# main.net
KiCad netlist of a schematic drawn in EAGLE
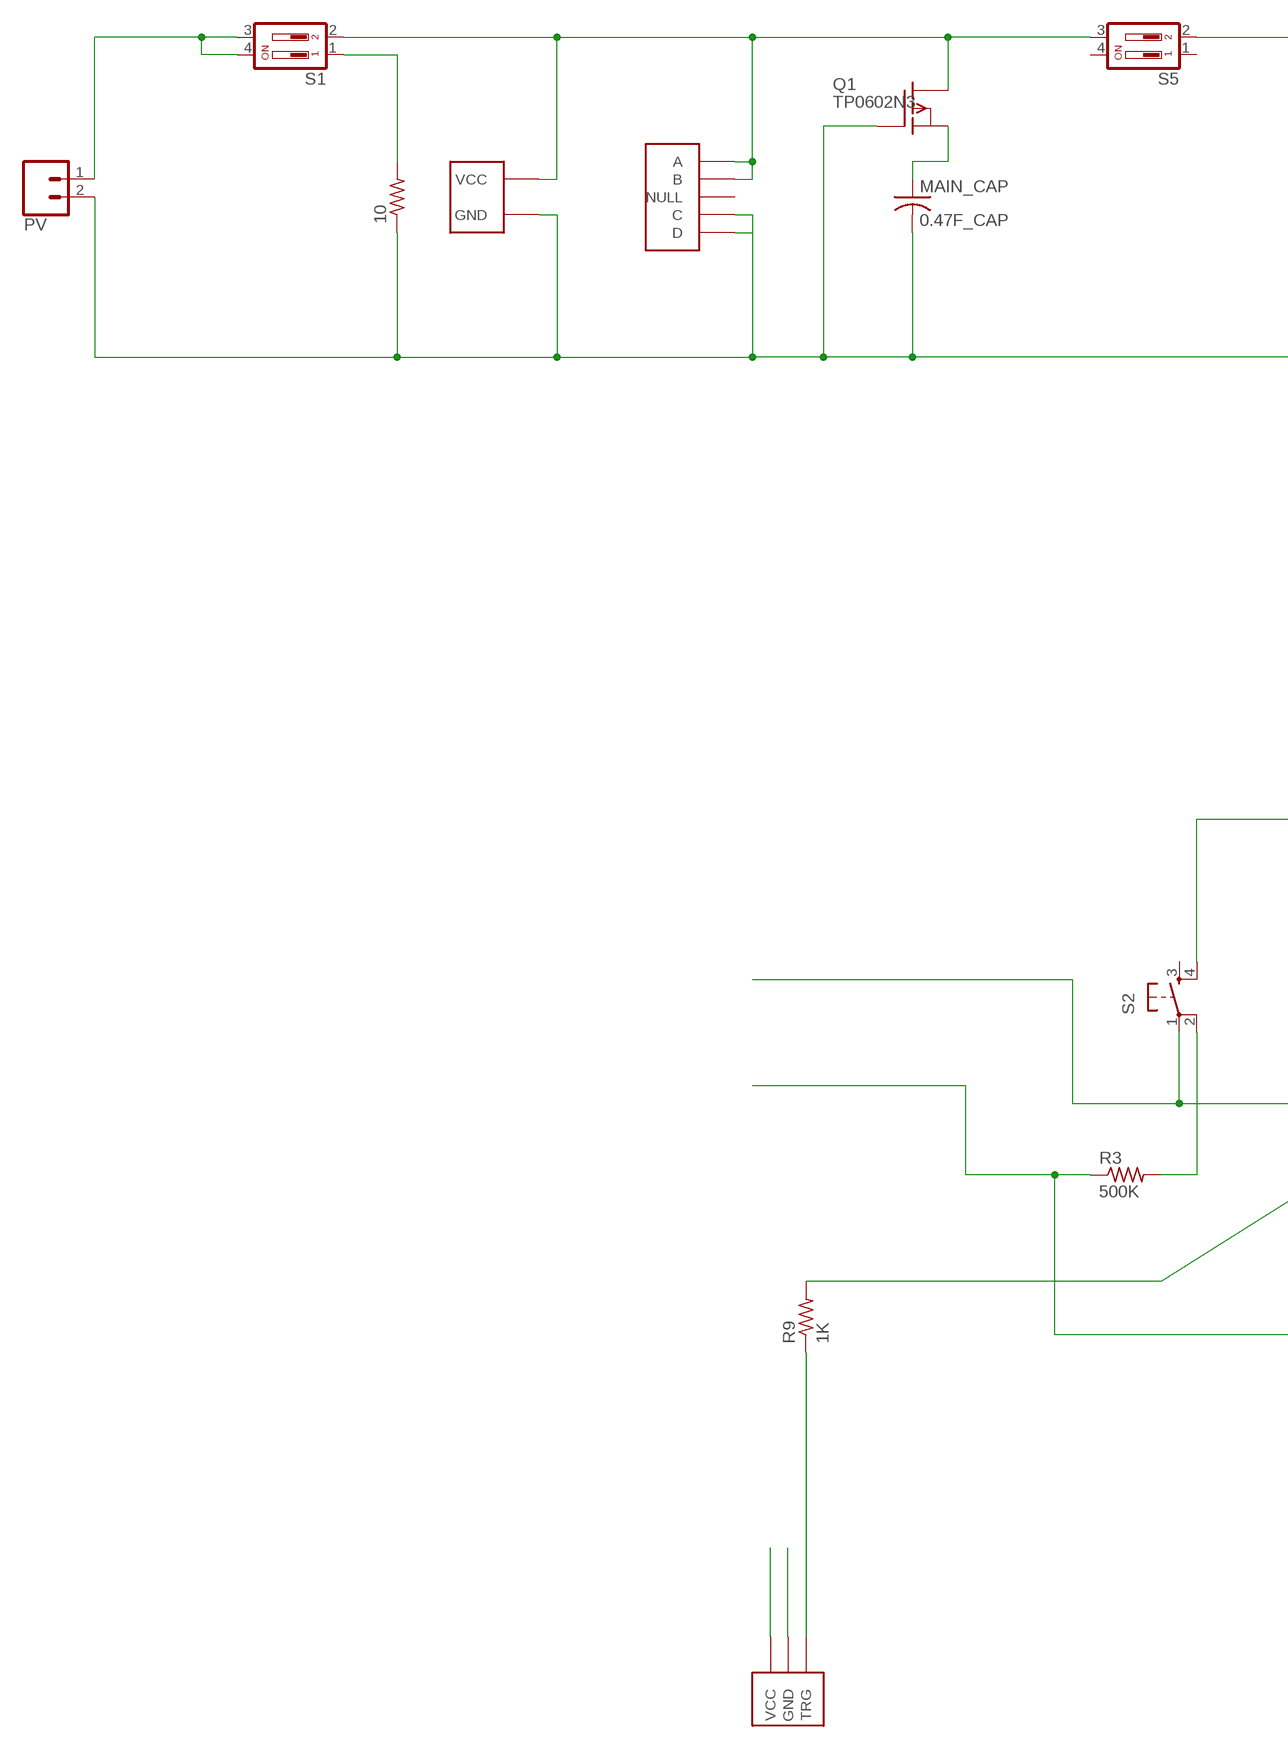
[diagram p0: schematic, sheet 1, part 1 of 2]
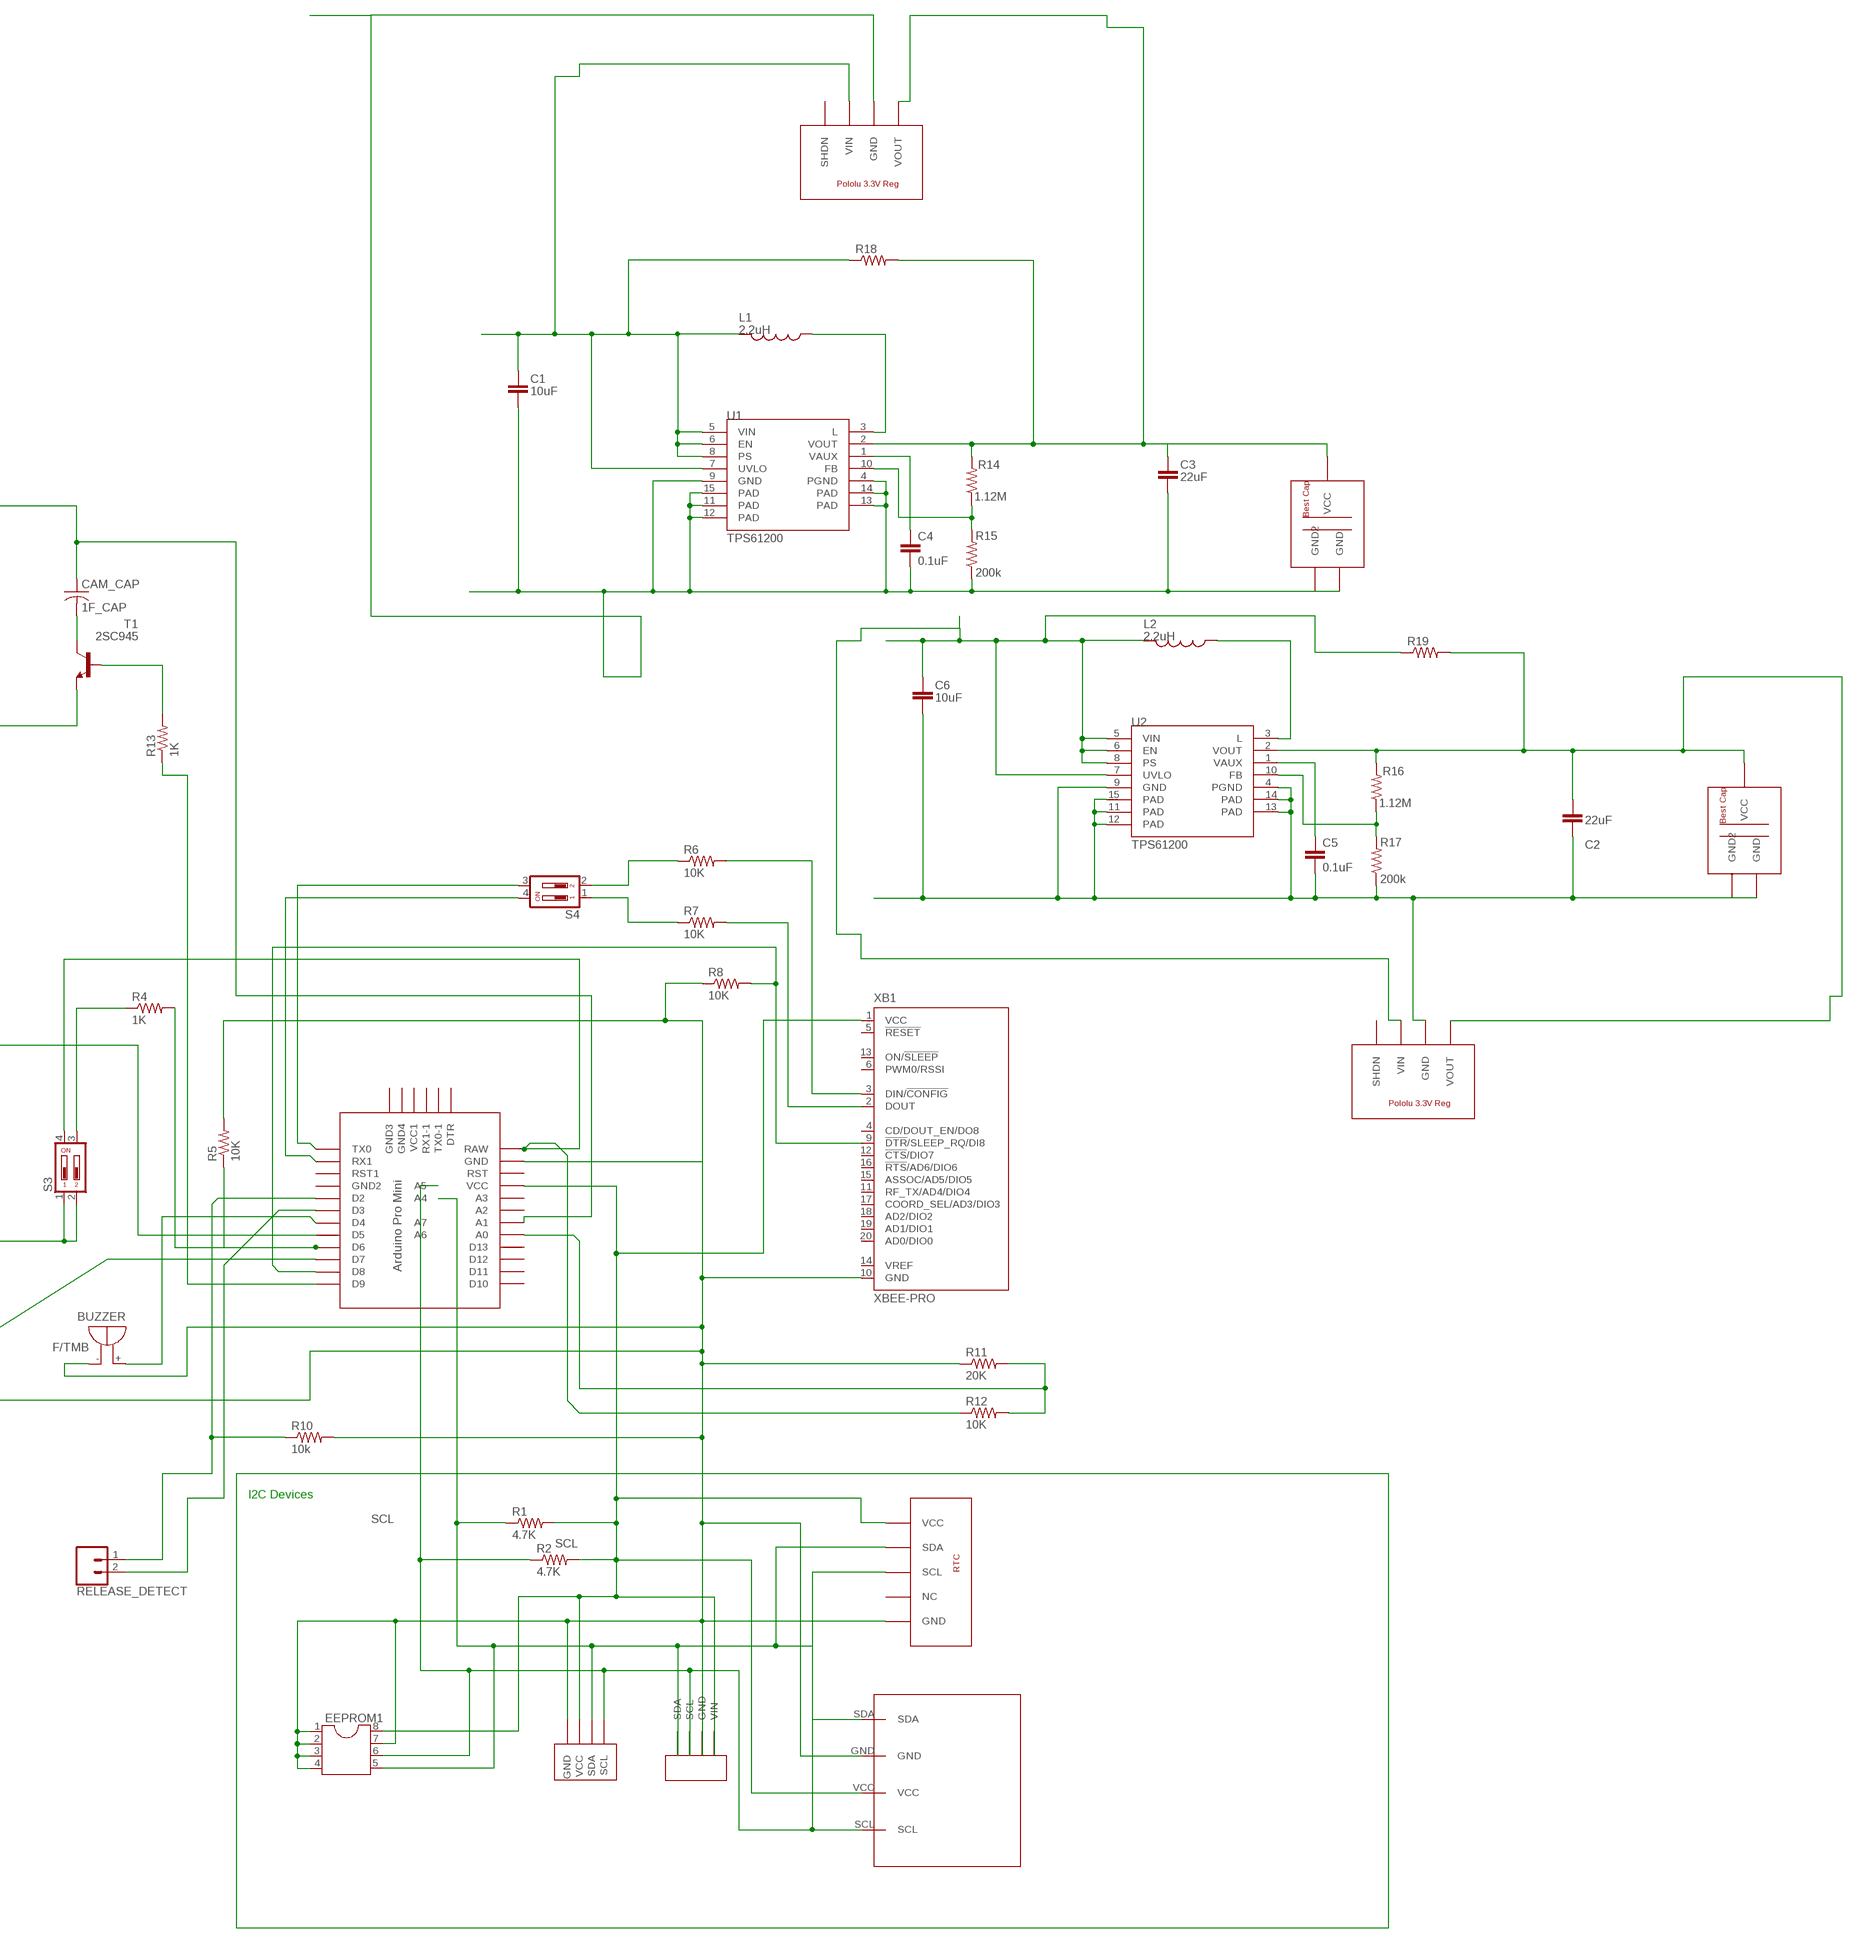
[diagram p1: schematic, sheet 1, part 2 of 2]

(export (version "E")
  (design (tool "Eeschema 10.0.6"))
  (components
    (comp (ref "10")
      (value "R-US_M1206")
      (footprint "eagle-import:M1206")
      (libsource (lib "eagle-import") (part "R-US_M1206"))
    )
    (comp (ref "BUZZER")
      (value "F/TMB")
      (footprint "eagle-import:F_TMB")
      (libsource (lib "eagle-import") (part "F/TMB"))
    )
    (comp (ref "C1")
      (value "10uF")
      (footprint "eagle-import:0805")
      (libsource (lib "eagle-import") (part "CAP0805"))
    )
    (comp (ref "C2")
      (value "22uF")
      (footprint "eagle-import:0805")
      (libsource (lib "eagle-import") (part "CAP0805"))
    )
    (comp (ref "C3")
      (value "22uF")
      (footprint "eagle-import:0805")
      (libsource (lib "eagle-import") (part "CAP0805"))
    )
    (comp (ref "C4")
      (value "0.1uF")
      (footprint "eagle-import:0805")
      (libsource (lib "eagle-import") (part "SparkFun_CAP0805"))
    )
    (comp (ref "C5")
      (value "0.1uF")
      (footprint "eagle-import:0805")
      (libsource (lib "eagle-import") (part "SparkFun_CAP0805"))
    )
    (comp (ref "C6")
      (value "10uF")
      (footprint "eagle-import:0805")
      (libsource (lib "eagle-import") (part "CAP0805"))
    )
    (comp (ref "CAM_CAP")
      (value "1F_CAP")
      (footprint "eagle-import:1F_CAP")
      (libsource (lib "eagle-import") (part "1F_CAP"))
    )
    (comp (ref "EEPROM1")
      (value "DIL8S")
      (footprint "eagle-import:SOCKET-08")
      (libsource (lib "eagle-import") (part "DIL8S"))
    )
    (comp (ref "L1")
      (value "2.2uH")
      (footprint "eagle-import:1212")
      (libsource (lib "eagle-import") (part "INDUCTOR_LIP"))
    )
    (comp (ref "L2")
      (value "2.2uH")
      (footprint "eagle-import:1212")
      (libsource (lib "eagle-import") (part "INDUCTOR_LIP"))
    )
    (comp (ref "MAIN_CAP")
      (value "0.47F_CAP")
      (footprint "eagle-import:0.47F_CAP")
      (libsource (lib "eagle-import") (part "0.47F_CAP"))
    )
    (comp (ref "PITOTTUBE")
      (value "SENSIRION")
      (footprint "eagle-import:SENSIRIONSDP810")
      (libsource (lib "eagle-import") (part "SENSIRION"))
    )
    (comp (ref "PV")
      (value "CONN_02")
      (footprint "eagle-import:1X02")
      (libsource (lib "eagle-import") (part "CONN_02"))
    )
    (comp (ref "Q1")
      (value "TP0602N3")
      (footprint "eagle-import:TO-92")
      (libsource (lib "eagle-import") (part "TP0602N3"))
    )
    (comp (ref "R1")
      (value "4.7K")
      (footprint "eagle-import:M0805")
      (libsource (lib "eagle-import") (part "R-US_M0805"))
    )
    (comp (ref "R2")
      (value "4.7K")
      (footprint "eagle-import:M0805")
      (libsource (lib "eagle-import") (part "R-US_M0805"))
    )
    (comp (ref "R3")
      (value "500K")
      (footprint "eagle-import:M0805")
      (libsource (lib "eagle-import") (part "R-US_M0805"))
    )
    (comp (ref "R4")
      (value "1K")
      (footprint "eagle-import:M0805")
      (libsource (lib "eagle-import") (part "R-US_M0805"))
    )
    (comp (ref "R5")
      (value "10K")
      (footprint "eagle-import:M0805")
      (libsource (lib "eagle-import") (part "R-US_M0805"))
    )
    (comp (ref "R6")
      (value "10K")
      (footprint "eagle-import:R0805")
      (libsource (lib "eagle-import") (part "R-US_R0805"))
    )
    (comp (ref "R7")
      (value "10K")
      (footprint "eagle-import:R0805")
      (libsource (lib "eagle-import") (part "R-US_R0805"))
    )
    (comp (ref "R8")
      (value "10K")
      (footprint "eagle-import:R0805")
      (libsource (lib "eagle-import") (part "R-US_R0805"))
    )
    (comp (ref "R9")
      (value "1K")
      (footprint "eagle-import:R0805")
      (libsource (lib "eagle-import") (part "R-US_R0805"))
    )
    (comp (ref "R10")
      (value "10k")
      (footprint "eagle-import:R0805")
      (libsource (lib "eagle-import") (part "R-US_R0805"))
    )
    (comp (ref "R11")
      (value "20K")
      (footprint "eagle-import:R0805")
      (libsource (lib "eagle-import") (part "R-US_R0805"))
    )
    (comp (ref "R12")
      (value "10K")
      (footprint "eagle-import:R0805")
      (libsource (lib "eagle-import") (part "R-US_R0805"))
    )
    (comp (ref "R13")
      (value "1K")
      (footprint "eagle-import:M0805")
      (libsource (lib "eagle-import") (part "resistor_348_R-US_M0805"))
    )
    (comp (ref "R14")
      (value "1.12M")
      (footprint "eagle-import:0805")
      (libsource (lib "eagle-import") (part "RESISTOR0805-RES"))
    )
    (comp (ref "R15")
      (value "200k")
      (footprint "eagle-import:0805")
      (libsource (lib "eagle-import") (part "RESISTOR0805-RES"))
    )
    (comp (ref "R16")
      (value "1.12M")
      (footprint "eagle-import:0805")
      (libsource (lib "eagle-import") (part "RESISTOR0805-RES"))
    )
    (comp (ref "R17")
      (value "200k")
      (footprint "eagle-import:0805")
      (libsource (lib "eagle-import") (part "RESISTOR0805-RES"))
    )
    (comp (ref "R18")
      (value "R-US_M0805")
      (footprint "eagle-import:M0805")
      (libsource (lib "eagle-import") (part "resistor_348_R-US_M0805"))
    )
    (comp (ref "R19")
      (value "R-US_R0805")
      (footprint "eagle-import:R0805")
      (libsource (lib "eagle-import") (part "resistor_348_R-US_R0805"))
    )
    (comp (ref "RELEASE_DETECT")
      (value "CONN_02")
      (footprint "eagle-import:1X02")
      (libsource (lib "eagle-import") (part "CONN_02"))
    )
    (comp (ref "S1")
      (value "DP02")
      (footprint "eagle-import:DP-02")
      (fields (field (name "MPN") "MCDP02"))
      (libsource (lib "eagle-import") (part "DP02"))
    )
    (comp (ref "S2")
      (value "TAC_SWITCHPTH")
      (footprint "eagle-import:TACTILE-PTH")
      (libsource (lib "eagle-import") (part "TAC_SWITCHPTH"))
    )
    (comp (ref "S3")
      (value "DP02")
      (footprint "eagle-import:DP-02")
      (fields (field (name "MPN") "MCDP02"))
      (libsource (lib "eagle-import") (part "DP02"))
    )
    (comp (ref "S4")
      (value "DP02")
      (footprint "eagle-import:DP-02")
      (fields (field (name "MPN") "MCDP02"))
      (libsource (lib "eagle-import") (part "DP02"))
    )
    (comp (ref "S5")
      (value "DP02")
      (footprint "eagle-import:DP-02")
      (fields (field (name "MPN") "MCDP02"))
      (libsource (lib "eagle-import") (part "DP02"))
    )
    (comp (ref "T1")
      (value "2SC945")
      (footprint "eagle-import:TO92-ECB")
      (libsource (lib "eagle-import") (part "2SC945"))
    )
    (comp (ref "U$1")
      (value "PRO-MINI-2")
      (footprint "eagle-import:PRO-MINI-2")
      (libsource (lib "eagle-import") (part "PRO-MINI-2"))
    )
    (comp (ref "U$2")
      (value "HMC883L_BREAKOUT")
      (footprint "eagle-import:HMC5833L_BREAKOUT")
      (libsource (lib "eagle-import") (part "HMC883L_BREAKOUT"))
    )
    (comp (ref "U$3")
      (value "BMP180_BREAKOUT")
      (footprint "eagle-import:BMP180_BREAKOUT")
      (libsource (lib "eagle-import") (part "BMP180_BREAKOUT"))
    )
    (comp (ref "U$4")
      (value "CAMERA_BREAKOUT")
      (footprint "eagle-import:CAMERA")
      (libsource (lib "eagle-import") (part "CAMERA_BREAKOUT"))
    )
    (comp (ref "U$5")
      (value "EXT_PWR")
      (footprint "eagle-import:EXTERNALPOWER")
      (libsource (lib "eagle-import") (part "EXT_PWR"))
    )
    (comp (ref "U$6")
      (value "VOLTMETER")
      (footprint "eagle-import:VOLTMETER")
      (libsource (lib "eagle-import") (part "VOLTMETER"))
    )
    (comp (ref "U$7")
      (value "RTC")
      (footprint "eagle-import:RTC")
      (libsource (lib "eagle-import") (part "RTC"))
    )
    (comp (ref "U$8")
      (value "BESTCAP")
      (footprint "eagle-import:BESTCAP")
      (libsource (lib "eagle-import") (part "BESTCAP"))
    )
    (comp (ref "U$9")
      (value "BESTCAP")
      (footprint "eagle-import:BESTCAP")
      (libsource (lib "eagle-import") (part "BESTCAP"))
    )
    (comp (ref "U$10")
      (value "POLOLU3VREG")
      (footprint "eagle-import:POLOLU3VREG")
      (libsource (lib "eagle-import") (part "POLOLU3VREG"))
    )
    (comp (ref "U$11")
      (value "POLOLU3VREG")
      (footprint "eagle-import:POLOLU3VREG")
      (libsource (lib "eagle-import") (part "POLOLU3VREG"))
    )
    (comp (ref "U1")
      (value "TPS61200")
      (footprint "eagle-import:QFN-10_PAD")
      (libsource (lib "eagle-import") (part "TPS61200"))
    )
    (comp (ref "U2")
      (value "TPS61200")
      (footprint "eagle-import:QFN-10_PAD")
      (libsource (lib "eagle-import") (part "TPS61200"))
    )
    (comp (ref "XB1")
      (value "XBEE-PRO")
      (footprint "eagle-import:XBEE-PRO")
      (fields (field (name "MPN") "XBP24-AWI-001"))
      (libsource (lib "eagle-import") (part "XBEE-PRO"))
    )
  )
  (nets
    (net (code "1") (name "/CAM_VIN") (class "Default")
      (node (ref "C2") (pin "1") (pinfunction "1_1") (pintype "passive"))
      (node (ref "R16") (pin "2") (pinfunction "2_2") (pintype "passive"))
      (node (ref "R19") (pin "2") (pinfunction "2_2") (pintype "passive"))
      (node (ref "U$11") (pin "VOUT") (pinfunction "VOUT_VOUT") (pintype "bidirectional"))
      (node (ref "U$4") (pin "VCC") (pinfunction "VCC_VCC") (pintype "bidirectional"))
      (node (ref "U$9") (pin "VCC") (pinfunction "VCC_VCC") (pintype "bidirectional"))
      (node (ref "U2") (pin "2") (pinfunction "VOUT_2") (pintype "passive"))
    )
    (net (code "2") (name "/CAP_VIN") (class "Default")
      (node (ref "C6") (pin "1") (pinfunction "1_1") (pintype "passive"))
      (node (ref "CAM_CAP") (pin "+") (pinfunction "+_+") (pintype "passive"))
      (node (ref "L2") (pin "P$2") (pinfunction "2_P$2") (pintype "passive"))
      (node (ref "R19") (pin "1") (pinfunction "1_1") (pintype "passive"))
      (node (ref "S5") (pin "2") (pinfunction "2_2") (pintype "passive"))
      (node (ref "U$1") (pin "A1") (pinfunction "A1_A1") (pintype "bidirectional"))
      (node (ref "U$11") (pin "VIN") (pinfunction "VIN_VIN") (pintype "bidirectional"))
      (node (ref "U2") (pin "5") (pinfunction "VIN_5") (pintype "power_in"))
      (node (ref "U2") (pin "6") (pinfunction "EN_6") (pintype "input"))
      (node (ref "U2") (pin "7") (pinfunction "UVLO_7") (pintype "passive"))
      (node (ref "U2") (pin "8") (pinfunction "PS_8") (pintype "input"))
    )
    (net (code "3") (name "/GND") (class "Default")
      (node (ref "10") (pin "1") (pinfunction "1_1") (pintype "passive"))
      (node (ref "BUZZER") (pin "-") (pinfunction "-_-") (pintype "passive"))
      (node (ref "C1") (pin "2") (pinfunction "2_2") (pintype "passive"))
      (node (ref "C2") (pin "2") (pinfunction "2_2") (pintype "passive"))
      (node (ref "C3") (pin "2") (pinfunction "2_2") (pintype "passive"))
      (node (ref "C4") (pin "2") (pinfunction "2_2") (pintype "passive"))
      (node (ref "C5") (pin "2") (pinfunction "2_2") (pintype "passive"))
      (node (ref "C6") (pin "2") (pinfunction "2_2") (pintype "passive"))
      (node (ref "EEPROM1") (pin "1") (pinfunction "1_1") (pintype "passive"))
      (node (ref "EEPROM1") (pin "2") (pinfunction "2_2") (pintype "passive"))
      (node (ref "EEPROM1") (pin "3") (pinfunction "3_3") (pintype "passive"))
      (node (ref "EEPROM1") (pin "4") (pinfunction "4_4") (pintype "passive"))
      (node (ref "EEPROM1") (pin "7") (pinfunction "7_7") (pintype "passive"))
      (node (ref "MAIN_CAP") (pin "-") (pinfunction "-_-") (pintype "passive"))
      (node (ref "PITOTTUBE") (pin "GND") (pinfunction "GND_GND") (pintype "bidirectional"))
      (node (ref "PV") (pin "2") (pinfunction "2_2") (pintype "passive"))
      (node (ref "Q1") (pin "2") (pinfunction "G_2") (pintype "passive"))
      (node (ref "R10") (pin "2") (pinfunction "2_2") (pintype "passive"))
      (node (ref "R11") (pin "1") (pinfunction "1_1") (pintype "passive"))
      (node (ref "R15") (pin "1") (pinfunction "1_1") (pintype "passive"))
      (node (ref "R17") (pin "1") (pinfunction "1_1") (pintype "passive"))
      (node (ref "R3") (pin "1") (pinfunction "1_1") (pintype "passive"))
      (node (ref "R5") (pin "2") (pinfunction "2_2") (pintype "passive"))
      (node (ref "R8") (pin "1") (pinfunction "1_1") (pintype "passive"))
      (node (ref "T1") (pin "E") (pinfunction "E_E") (pintype "passive"))
      (node (ref "U$1") (pin "GND") (pinfunction "GND_GND") (pintype "bidirectional"))
      (node (ref "U$10") (pin "GND") (pinfunction "GND_GND") (pintype "bidirectional"))
      (node (ref "U$11") (pin "GND") (pinfunction "GND_GND") (pintype "bidirectional"))
      (node (ref "U$2") (pin "GND") (pinfunction "GND_GND") (pintype "bidirectional"))
      (node (ref "U$3") (pin "GND") (pinfunction "GND_GND") (pintype "bidirectional"))
      (node (ref "U$4") (pin "GND") (pinfunction "GND_GND") (pintype "bidirectional"))
      (node (ref "U$5") (pin "GND") (pinfunction "GND_GND") (pintype "bidirectional"))
      (node (ref "U$6") (pin "C") (pinfunction "C_C") (pintype "bidirectional"))
      (node (ref "U$6") (pin "D") (pinfunction "D_D") (pintype "bidirectional"))
      (node (ref "U$7") (pin "GND") (pinfunction "GND_GND") (pintype "bidirectional"))
      (node (ref "U$8") (pin "GND") (pinfunction "GND_GND") (pintype "bidirectional"))
      (node (ref "U$8") (pin "GND2") (pinfunction "GND2_GND2") (pintype "bidirectional"))
      (node (ref "U$9") (pin "GND") (pinfunction "GND_GND") (pintype "bidirectional"))
      (node (ref "U$9") (pin "GND2") (pinfunction "GND2_GND2") (pintype "bidirectional"))
      (node (ref "U1") (pin "11") (pinfunction "PAD_11") (pintype "power_in"))
      (node (ref "U1") (pin "12") (pinfunction "PAD_12") (pintype "power_in"))
      (node (ref "U1") (pin "13") (pinfunction "PAD_13") (pintype "power_in"))
      (node (ref "U1") (pin "14") (pinfunction "PAD_14") (pintype "power_in"))
      (node (ref "U1") (pin "15") (pinfunction "PAD_15") (pintype "power_in"))
      (node (ref "U1") (pin "4") (pinfunction "PGND_4") (pintype "power_in"))
      (node (ref "U1") (pin "9") (pinfunction "GND_9") (pintype "power_in"))
      (node (ref "U2") (pin "11") (pinfunction "PAD_11") (pintype "power_in"))
      (node (ref "U2") (pin "12") (pinfunction "PAD_12") (pintype "power_in"))
      (node (ref "U2") (pin "13") (pinfunction "PAD_13") (pintype "power_in"))
      (node (ref "U2") (pin "14") (pinfunction "PAD_14") (pintype "power_in"))
      (node (ref "U2") (pin "15") (pinfunction "PAD_15") (pintype "power_in"))
      (node (ref "U2") (pin "4") (pinfunction "PGND_4") (pintype "power_in"))
      (node (ref "U2") (pin "9") (pinfunction "GND_9") (pintype "power_in"))
      (node (ref "XB1") (pin "10") (pinfunction "GND_10") (pintype "power_in"))
    )
    (net (code "4") (name "/MAIN_VIN") (class "Default")
      (node (ref "C3") (pin "1") (pinfunction "1_1") (pintype "passive"))
      (node (ref "R14") (pin "2") (pinfunction "2_2") (pintype "passive"))
      (node (ref "R18") (pin "2") (pinfunction "2_2") (pintype "passive"))
      (node (ref "S2") (pin "1") (pinfunction "1_1") (pintype "passive"))
      (node (ref "S3") (pin "1") (pinfunction "1_1") (pintype "passive"))
      (node (ref "S3") (pin "2") (pinfunction "2_2") (pintype "passive"))
      (node (ref "U$10") (pin "VOUT") (pinfunction "VOUT_VOUT") (pintype "bidirectional"))
      (node (ref "U$8") (pin "VCC") (pinfunction "VCC_VCC") (pintype "bidirectional"))
      (node (ref "U1") (pin "2") (pinfunction "VOUT_2") (pintype "passive"))
    )
    (net (code "5") (name "/SCL") (class "Default")
      (node (ref "EEPROM1") (pin "6") (pinfunction "6_6") (pintype "passive"))
      (node (ref "PITOTTUBE") (pin "SCL") (pinfunction "SCL_SCL") (pintype "bidirectional"))
      (node (ref "R2") (pin "1") (pinfunction "1_1") (pintype "passive"))
      (node (ref "U$1") (pin "A5") (pinfunction "A5_A5") (pintype "bidirectional"))
      (node (ref "U$2") (pin "SCL") (pinfunction "SCL_SCL") (pintype "bidirectional"))
      (node (ref "U$3") (pin "SCL") (pinfunction "SCL_SCL") (pintype "bidirectional"))
      (node (ref "U$7") (pin "SCL") (pinfunction "SCL_SCL") (pintype "bidirectional"))
    )
    (net (code "6") (name "/VIN") (class "Default")
      (node (ref "C1") (pin "1") (pinfunction "1_1") (pintype "passive"))
      (node (ref "L1") (pin "P$2") (pinfunction "2_P$2") (pintype "passive"))
      (node (ref "MAIN_CAP") (pin "+") (pinfunction "+_+") (pintype "passive"))
      (node (ref "Q1") (pin "1") (pinfunction "S_1") (pintype "passive"))
      (node (ref "R18") (pin "1") (pinfunction "1_1") (pintype "passive"))
      (node (ref "U$10") (pin "VIN") (pinfunction "VIN_VIN") (pintype "bidirectional"))
      (node (ref "U1") (pin "5") (pinfunction "VIN_5") (pintype "power_in"))
      (node (ref "U1") (pin "6") (pinfunction "EN_6") (pintype "input"))
      (node (ref "U1") (pin "7") (pinfunction "UVLO_7") (pintype "passive"))
      (node (ref "U1") (pin "8") (pinfunction "PS_8") (pintype "input"))
    )
    (net (code "7") (name "Net-(10-Pad2)") (class "Default")
      (node (ref "10") (pin "2") (pinfunction "2_2") (pintype "passive"))
      (node (ref "S1") (pin "1") (pinfunction "1_1") (pintype "passive"))
    )
    (net (code "8") (name "Net-(BUZZER-Pad+)") (class "Default")
      (node (ref "BUZZER") (pin "+") (pinfunction "+_+") (pintype "passive"))
      (node (ref "U$1") (pin "D4") (pinfunction "D4_D4") (pintype "bidirectional"))
    )
    (net (code "9") (name "Net-(CAM_CAP-Pad-)") (class "Default")
      (node (ref "CAM_CAP") (pin "-") (pinfunction "-_-") (pintype "passive"))
      (node (ref "T1") (pin "C") (pinfunction "C_C") (pintype "passive"))
    )
    (net (code "10") (name "Net-(EEPROM1-Pad5)") (class "Default")
      (node (ref "EEPROM1") (pin "5") (pinfunction "5_5") (pintype "passive"))
      (node (ref "PITOTTUBE") (pin "SDA") (pinfunction "SDA_SDA") (pintype "bidirectional"))
      (node (ref "R1") (pin "1") (pinfunction "1_1") (pintype "passive"))
      (node (ref "U$1") (pin "A4") (pinfunction "A4_A4") (pintype "bidirectional"))
      (node (ref "U$2") (pin "SDA") (pinfunction "SDA_SDA") (pintype "bidirectional"))
      (node (ref "U$3") (pin "SDA") (pinfunction "SDA_SDA") (pintype "bidirectional"))
      (node (ref "U$7") (pin "SDA") (pinfunction "SDA_SDA") (pintype "bidirectional"))
    )
    (net (code "11") (name "Net-(L1-1)") (class "Default")
      (node (ref "L1") (pin "P$1") (pinfunction "1_P$1") (pintype "passive"))
      (node (ref "U1") (pin "3") (pinfunction "L_3") (pintype "passive"))
    )
    (net (code "12") (name "Net-(L2-1)") (class "Default")
      (node (ref "L2") (pin "P$1") (pinfunction "1_P$1") (pintype "passive"))
      (node (ref "U2") (pin "3") (pinfunction "L_3") (pintype "passive"))
    )
    (net (code "13") (name "Net-(PV-Pad1)") (class "Default")
      (node (ref "PV") (pin "1") (pinfunction "1_1") (pintype "passive"))
      (node (ref "S1") (pin "3") (pinfunction "3_3") (pintype "passive"))
      (node (ref "S1") (pin "4") (pinfunction "4_4") (pintype "passive"))
    )
    (net (code "14") (name "Net-(Q1-D)") (class "Default")
      (node (ref "Q1") (pin "3") (pinfunction "D_3") (pintype "passive"))
      (node (ref "S1") (pin "2") (pinfunction "2_2") (pintype "passive"))
      (node (ref "S5") (pin "3") (pinfunction "3_3") (pintype "passive"))
      (node (ref "U$5") (pin "VCC") (pinfunction "VCC_VCC") (pintype "bidirectional"))
      (node (ref "U$6") (pin "A") (pinfunction "A_A") (pintype "bidirectional"))
      (node (ref "U$6") (pin "B") (pinfunction "B_B") (pintype "bidirectional"))
    )
    (net (code "15") (name "Net-(R3-Pad2)") (class "Default")
      (node (ref "R3") (pin "2") (pinfunction "2_2") (pintype "passive"))
      (node (ref "S2") (pin "2") (pinfunction "2_2") (pintype "passive"))
    )
    (net (code "16") (name "Net-(R4-Pad1)") (class "Default")
      (node (ref "R4") (pin "1") (pinfunction "1_1") (pintype "passive"))
      (node (ref "S3") (pin "3") (pinfunction "3_3") (pintype "passive"))
    )
    (net (code "17") (name "Net-(R4-Pad2)") (class "Default")
      (node (ref "R4") (pin "2") (pinfunction "2_2") (pintype "passive"))
      (node (ref "R5") (pin "1") (pinfunction "1_1") (pintype "passive"))
      (node (ref "U$1") (pin "D6") (pinfunction "D6_D6") (pintype "bidirectional"))
    )
    (net (code "18") (name "Net-(R6-Pad1)") (class "Default")
      (node (ref "R6") (pin "1") (pinfunction "1_1") (pintype "passive"))
      (node (ref "S4") (pin "2") (pinfunction "2_2") (pintype "passive"))
    )
    (net (code "19") (name "Net-(R7-Pad1)") (class "Default")
      (node (ref "R7") (pin "1") (pinfunction "1_1") (pintype "passive"))
      (node (ref "S4") (pin "1") (pinfunction "1_1") (pintype "passive"))
    )
    (net (code "20") (name "Net-(R9-Pad1)") (class "Default")
      (node (ref "R9") (pin "1") (pinfunction "1_1") (pintype "passive"))
      (node (ref "U$4") (pin "TRG") (pinfunction "TRG_TRG") (pintype "bidirectional"))
    )
    (net (code "21") (name "Net-(R9-Pad2)") (class "Default")
      (node (ref "R9") (pin "2") (pinfunction "2_2") (pintype "passive"))
      (node (ref "U$1") (pin "D7") (pinfunction "D7_D7") (pintype "bidirectional"))
    )
    (net (code "22") (name "Net-(R10-Pad1)") (class "Default")
      (node (ref "R10") (pin "1") (pinfunction "1_1") (pintype "passive"))
      (node (ref "RELEASE_DETECT") (pin "1") (pinfunction "1_1") (pintype "passive"))
      (node (ref "U$1") (pin "D2") (pinfunction "D2_D2") (pintype "bidirectional"))
    )
    (net (code "23") (name "Net-(R11-Pad2)") (class "Default")
      (node (ref "R11") (pin "2") (pinfunction "2_2") (pintype "passive"))
      (node (ref "R12") (pin "2") (pinfunction "2_2") (pintype "passive"))
      (node (ref "U$1") (pin "A0") (pinfunction "A0_A0") (pintype "bidirectional"))
    )
    (net (code "24") (name "Net-(R12-Pad1)") (class "Default")
      (node (ref "R12") (pin "1") (pinfunction "1_1") (pintype "passive"))
      (node (ref "S3") (pin "4") (pinfunction "4_4") (pintype "passive"))
      (node (ref "U$1") (pin "RAW") (pinfunction "RAW_RAW") (pintype "bidirectional"))
    )
    (net (code "25") (name "Net-(R13-Pad1)") (class "Default")
      (node (ref "R13") (pin "1") (pinfunction "1_1") (pintype "passive"))
      (node (ref "U$1") (pin "D9") (pinfunction "D9_D9") (pintype "bidirectional"))
    )
    (net (code "26") (name "Net-(R13-Pad2)") (class "Default")
      (node (ref "R13") (pin "2") (pinfunction "2_2") (pintype "passive"))
      (node (ref "T1") (pin "B") (pinfunction "B_B") (pintype "passive"))
    )
    (net (code "27") (name "Net-(RELEASE_DETECT-Pad2)") (class "Default")
      (node (ref "RELEASE_DETECT") (pin "2") (pinfunction "2_2") (pintype "passive"))
      (node (ref "U$1") (pin "D3") (pinfunction "D3_D3") (pintype "bidirectional"))
    )
    (net (code "28") (name "Net-(S2-Pad4)") (class "Default")
      (node (ref "S2") (pin "4") (pinfunction "4_4") (pintype "passive"))
      (node (ref "U$1") (pin "D5") (pinfunction "D5_D5") (pintype "bidirectional"))
    )
    (net (code "29") (name "Net-(S4-Pad3)") (class "Default")
      (node (ref "S4") (pin "3") (pinfunction "3_3") (pintype "passive"))
      (node (ref "U$1") (pin "TX0") (pinfunction "TX0_TX0") (pintype "bidirectional"))
    )
    (net (code "30") (name "Net-(S4-Pad4)") (class "Default")
      (node (ref "S4") (pin "4") (pinfunction "4_4") (pintype "passive"))
      (node (ref "U$1") (pin "RX1") (pinfunction "RX1_RX1") (pintype "bidirectional"))
    )
    (net (code "31") (name "Net-(U1-FB)") (class "Default")
      (node (ref "R14") (pin "1") (pinfunction "1_1") (pintype "passive"))
      (node (ref "R15") (pin "2") (pinfunction "2_2") (pintype "passive"))
      (node (ref "U1") (pin "10") (pinfunction "FB_10") (pintype "passive"))
    )
    (net (code "32") (name "Net-(U1-VAUX)") (class "Default")
      (node (ref "C4") (pin "1") (pinfunction "1_1") (pintype "passive"))
      (node (ref "U1") (pin "1") (pinfunction "VAUX_1") (pintype "passive"))
    )
    (net (code "33") (name "Net-(U2-FB)") (class "Default")
      (node (ref "R16") (pin "1") (pinfunction "1_1") (pintype "passive"))
      (node (ref "R17") (pin "2") (pinfunction "2_2") (pintype "passive"))
      (node (ref "U2") (pin "10") (pinfunction "FB_10") (pintype "passive"))
    )
    (net (code "34") (name "Net-(U2-VAUX)") (class "Default")
      (node (ref "C5") (pin "1") (pinfunction "1_1") (pintype "passive"))
      (node (ref "U2") (pin "1") (pinfunction "VAUX_1") (pintype "passive"))
    )
    (net (code "35") (name "Net-(XB1-DIN{slash}~{CONFIG})") (class "Default")
      (node (ref "R6") (pin "2") (pinfunction "2_2") (pintype "passive"))
      (node (ref "XB1") (pin "3") (pinfunction "DIN/~{CONFIG}_3") (pintype "input"))
    )
    (net (code "36") (name "Net-(XB1-DOUT)") (class "Default")
      (node (ref "R7") (pin "2") (pinfunction "2_2") (pintype "passive"))
      (node (ref "XB1") (pin "2") (pinfunction "DOUT_2") (pintype "output"))
    )
    (net (code "37") (name "Net-(XB1-VCC)") (class "Default")
      (node (ref "EEPROM1") (pin "8") (pinfunction "8_8") (pintype "passive"))
      (node (ref "PITOTTUBE") (pin "VCC") (pinfunction "VCC_VCC") (pintype "bidirectional"))
      (node (ref "R1") (pin "2") (pinfunction "2_2") (pintype "passive"))
      (node (ref "R2") (pin "2") (pinfunction "2_2") (pintype "passive"))
      (node (ref "U$1") (pin "VCC") (pinfunction "VCC_VCC") (pintype "bidirectional"))
      (node (ref "U$2") (pin "VCC") (pinfunction "VCC_VCC") (pintype "bidirectional"))
      (node (ref "U$3") (pin "VIN") (pinfunction "VIN_VIN") (pintype "bidirectional"))
      (node (ref "U$7") (pin "VCC") (pinfunction "VCC_VCC") (pintype "bidirectional"))
      (node (ref "XB1") (pin "1") (pinfunction "VCC_1") (pintype "power_in"))
    )
    (net (code "38") (name "Net-(XB1-~{DTR}{slash}SLEEP_RQ{slash}DI8)") (class "Default")
      (node (ref "R8") (pin "2") (pinfunction "2_2") (pintype "passive"))
      (node (ref "U$1") (pin "D8") (pinfunction "D8_D8") (pintype "bidirectional"))
      (node (ref "XB1") (pin "9") (pinfunction "~{DTR}/SLEEP_RQ/DI8_9") (pintype "bidirectional"))
    )
    (net (code "39") (name "unconnected-(S2-Pad3)") (class "Default")
      (node (ref "S2") (pin "3") (pinfunction "3_3") (pintype "passive"))
    )
    (net (code "40") (name "unconnected-(S5-Pad1)") (class "Default")
      (node (ref "S5") (pin "1") (pinfunction "1_1") (pintype "passive"))
    )
    (net (code "41") (name "unconnected-(S5-Pad4)") (class "Default")
      (node (ref "S5") (pin "4") (pinfunction "4_4") (pintype "passive"))
    )
    (net (code "42") (name "unconnected-(U$1-GND2-PadGND1)") (class "Default")
      (node (ref "U$1") (pin "GND1") (pinfunction "GND2_GND1") (pintype "bidirectional"))
    )
    (net (code "43") (name "unconnected-(U$1-GND3-PadGND2)") (class "Default")
      (node (ref "U$1") (pin "GND2") (pinfunction "GND3_GND2") (pintype "bidirectional"))
    )
    (net (code "44") (name "unconnected-(U$1-GND4-PadGND3)") (class "Default")
      (node (ref "U$1") (pin "GND3") (pinfunction "GND4_GND3") (pintype "bidirectional"))
    )
    (net (code "45") (name "unconnected-(U$1-PadA2)") (class "Default")
      (node (ref "U$1") (pin "A2") (pinfunction "A2_A2") (pintype "bidirectional"))
    )
    (net (code "46") (name "unconnected-(U$1-PadA3)") (class "Default")
      (node (ref "U$1") (pin "A3") (pinfunction "A3_A3") (pintype "bidirectional"))
    )
    (net (code "47") (name "unconnected-(U$1-PadA6)") (class "Default")
      (node (ref "U$1") (pin "A6") (pinfunction "A6_A6") (pintype "bidirectional"))
    )
    (net (code "48") (name "unconnected-(U$1-PadA7)") (class "Default")
      (node (ref "U$1") (pin "A7") (pinfunction "A7_A7") (pintype "bidirectional"))
    )
    (net (code "49") (name "unconnected-(U$1-PadD10)") (class "Default")
      (node (ref "U$1") (pin "D10") (pinfunction "D10_D10") (pintype "bidirectional"))
    )
    (net (code "50") (name "unconnected-(U$1-PadD11)") (class "Default")
      (node (ref "U$1") (pin "D11") (pinfunction "D11_D11") (pintype "bidirectional"))
    )
    (net (code "51") (name "unconnected-(U$1-PadD12)") (class "Default")
      (node (ref "U$1") (pin "D12") (pinfunction "D12_D12") (pintype "bidirectional"))
    )
    (net (code "52") (name "unconnected-(U$1-PadD13)") (class "Default")
      (node (ref "U$1") (pin "D13") (pinfunction "D13_D13") (pintype "bidirectional"))
    )
    (net (code "53") (name "unconnected-(U$1-PadDTR)") (class "Default")
      (node (ref "U$1") (pin "DTR") (pinfunction "DTR_DTR") (pintype "bidirectional"))
    )
    (net (code "54") (name "unconnected-(U$1-PadRST)") (class "Default")
      (node (ref "U$1") (pin "RST") (pinfunction "RST_RST") (pintype "bidirectional"))
    )
    (net (code "55") (name "unconnected-(U$1-PadRST1)") (class "Default")
      (node (ref "U$1") (pin "RST1") (pinfunction "RST1_RST1") (pintype "bidirectional"))
    )
    (net (code "56") (name "unconnected-(U$1-PadRX1-1)") (class "Default")
      (node (ref "U$1") (pin "RX1-1") (pinfunction "RX1-1_RX1-1") (pintype "bidirectional"))
    )
    (net (code "57") (name "unconnected-(U$1-PadTX0-1)") (class "Default")
      (node (ref "U$1") (pin "TX0-1") (pinfunction "TX0-1_TX0-1") (pintype "bidirectional"))
    )
    (net (code "58") (name "unconnected-(U$1-PadVCC1)") (class "Default")
      (node (ref "U$1") (pin "VCC1") (pinfunction "VCC1_VCC1") (pintype "bidirectional"))
    )
    (net (code "59") (name "unconnected-(U$6-PadNULL)") (class "Default")
      (node (ref "U$6") (pin "NULL") (pinfunction "NULL_NULL") (pintype "bidirectional"))
    )
    (net (code "60") (name "unconnected-(U$7-PadNC)") (class "Default")
      (node (ref "U$7") (pin "NC") (pinfunction "NC_NC") (pintype "bidirectional"))
    )
    (net (code "61") (name "unconnected-(U$10-PadSHDN)") (class "Default")
      (node (ref "U$10") (pin "SHDN") (pinfunction "SHDN_SHDN") (pintype "bidirectional"))
    )
    (net (code "62") (name "unconnected-(U$11-PadSHDN)") (class "Default")
      (node (ref "U$11") (pin "SHDN") (pinfunction "SHDN_SHDN") (pintype "bidirectional"))
    )
    (net (code "63") (name "unconnected-(XB1-AD0{slash}DIO0-Pad20)") (class "Default")
      (node (ref "XB1") (pin "20") (pinfunction "AD0/DIO0_20") (pintype "bidirectional"))
    )
    (net (code "64") (name "unconnected-(XB1-AD1{slash}DIO1-Pad19)") (class "Default")
      (node (ref "XB1") (pin "19") (pinfunction "AD1/DIO1_19") (pintype "bidirectional"))
    )
    (net (code "65") (name "unconnected-(XB1-AD2{slash}DIO2-Pad18)") (class "Default")
      (node (ref "XB1") (pin "18") (pinfunction "AD2/DIO2_18") (pintype "bidirectional"))
    )
    (net (code "66") (name "unconnected-(XB1-ASSOC{slash}AD5{slash}DIO5-Pad15)") (class "Default")
      (node (ref "XB1") (pin "15") (pinfunction "ASSOC/AD5/DIO5_15") (pintype "bidirectional"))
    )
    (net (code "67") (name "unconnected-(XB1-CD{slash}DOUT_EN{slash}DO8-Pad4)") (class "Default")
      (node (ref "XB1") (pin "4") (pinfunction "CD/DOUT_EN/DO8_4") (pintype "output"))
    )
    (net (code "68") (name "unconnected-(XB1-COORD_SEL{slash}AD3{slash}DIO3-Pad17)") (class "Default")
      (node (ref "XB1") (pin "17") (pinfunction "COORD_SEL/AD3/DIO3_17") (pintype "bidirectional"))
    )
    (net (code "69") (name "unconnected-(XB1-ON{slash}~{SLEEP}-Pad13)") (class "Default")
      (node (ref "XB1") (pin "13") (pinfunction "ON/~{SLEEP}_13") (pintype "output"))
    )
    (net (code "70") (name "unconnected-(XB1-PWM0{slash}RSSI-Pad6)") (class "Default")
      (node (ref "XB1") (pin "6") (pinfunction "PWM0/RSSI_6") (pintype "output"))
    )
    (net (code "71") (name "unconnected-(XB1-RF_TX{slash}AD4{slash}DIO4-Pad11)") (class "Default")
      (node (ref "XB1") (pin "11") (pinfunction "RF_TX/AD4/DIO4_11") (pintype "bidirectional"))
    )
    (net (code "72") (name "unconnected-(XB1-VREF-Pad14)") (class "Default")
      (node (ref "XB1") (pin "14") (pinfunction "VREF_14") (pintype "input"))
    )
    (net (code "73") (name "unconnected-(XB1-~{CTS}{slash}DIO7-Pad12)") (class "Default")
      (node (ref "XB1") (pin "12") (pinfunction "~{CTS}/DIO7_12") (pintype "bidirectional"))
    )
    (net (code "74") (name "unconnected-(XB1-~{RESET}-Pad5)") (class "Default")
      (node (ref "XB1") (pin "5") (pinfunction "~{RESET}_5") (pintype "input"))
    )
    (net (code "75") (name "unconnected-(XB1-~{RTS}{slash}AD6{slash}DIO6-Pad16)") (class "Default")
      (node (ref "XB1") (pin "16") (pinfunction "~{RTS}/AD6/DIO6_16") (pintype "bidirectional"))
    )
  )
)
